# invert.net
KiCad netlist of a schematic drawn in Altium Designer
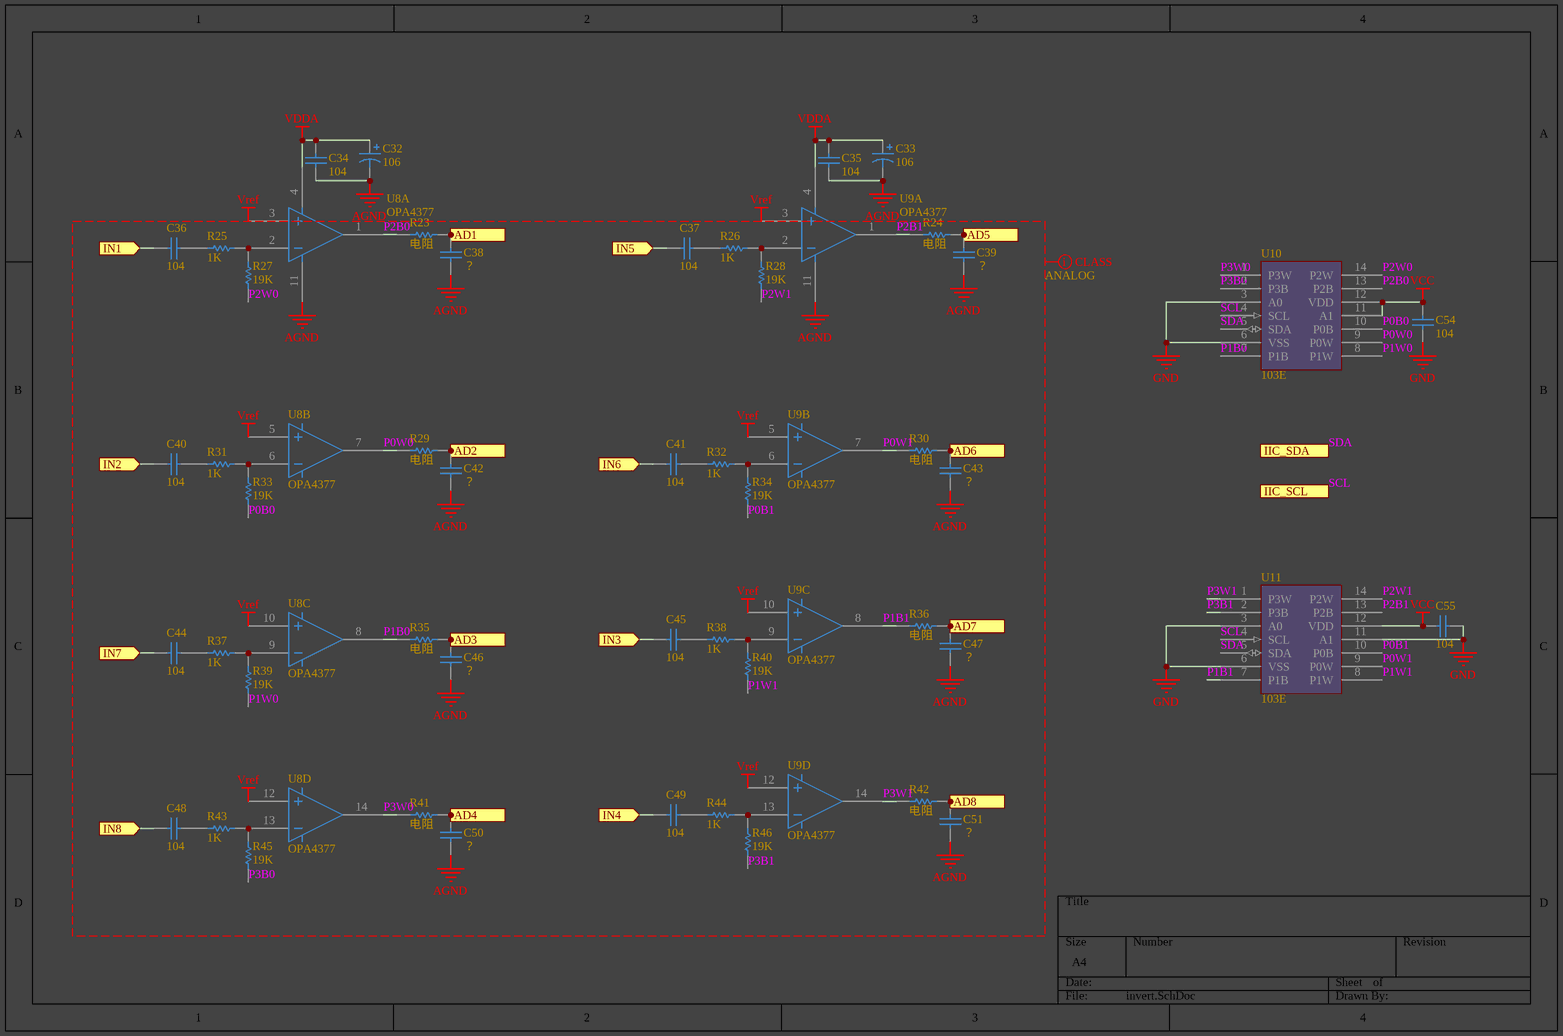
[diagram p0: invert.SchDoc]

(export (version "E")
  (design (tool "Eeschema 10.0.6"))
  (components
    (comp (ref "C32")
      (value "106")
      (footprint "3216-ce")
      (description "Polarized Capacitor (Axial)")
      (fields (field (name "PUBLISHER") "Altium Limited"))
      (libsource (lib "iMag") (part "电解电容"))
    )
    (comp (ref "C33")
      (value "106")
      (footprint "3216-ce")
      (description "Polarized Capacitor (Axial)")
      (fields (field (name "PUBLISHER") "Altium Limited"))
      (libsource (lib "iMag") (part "电解电容"))
    )
    (comp (ref "C34")
      (value "104")
      (footprint "C0402")
      (description "Capacitor")
      (fields (field (name "PUBLISHER") "Altium Limited"))
      (libsource (lib "iMag") (part "电容"))
    )
    (comp (ref "C35")
      (value "104")
      (footprint "C0402")
      (description "Capacitor")
      (fields (field (name "PUBLISHER") "Altium Limited"))
      (libsource (lib "iMag") (part "电容"))
    )
    (comp (ref "C36")
      (value "104")
      (footprint "C0402")
      (description "Capacitor")
      (fields (field (name "PUBLISHER") "Altium Limited"))
      (libsource (lib "iMag") (part "电容"))
    )
    (comp (ref "C37")
      (value "104")
      (footprint "C0402")
      (description "Capacitor")
      (fields (field (name "PUBLISHER") "Altium Limited"))
      (libsource (lib "iMag") (part "电容"))
    )
    (comp (ref "C38")
      (value "？")
      (footprint "C0402")
      (description "Capacitor")
      (fields (field (name "PUBLISHER") "Altium Limited"))
      (libsource (lib "iMag") (part "电容"))
    )
    (comp (ref "C39")
      (value "？")
      (footprint "C0402")
      (description "Capacitor")
      (fields (field (name "PUBLISHER") "Altium Limited"))
      (libsource (lib "iMag") (part "电容"))
    )
    (comp (ref "C40")
      (value "104")
      (footprint "C0402")
      (description "Capacitor")
      (fields (field (name "PUBLISHER") "Altium Limited"))
      (libsource (lib "iMag") (part "电容"))
    )
    (comp (ref "C41")
      (value "104")
      (footprint "C0402")
      (description "Capacitor")
      (fields (field (name "PUBLISHER") "Altium Limited"))
      (libsource (lib "iMag") (part "电容"))
    )
    (comp (ref "C42")
      (value "？")
      (footprint "C0402")
      (description "Capacitor")
      (fields (field (name "PUBLISHER") "Altium Limited"))
      (libsource (lib "iMag") (part "电容"))
    )
    (comp (ref "C43")
      (value "？")
      (footprint "C0402")
      (description "Capacitor")
      (fields (field (name "PUBLISHER") "Altium Limited"))
      (libsource (lib "iMag") (part "电容"))
    )
    (comp (ref "C44")
      (value "104")
      (footprint "C0402")
      (description "Capacitor")
      (fields (field (name "PUBLISHER") "Altium Limited"))
      (libsource (lib "iMag") (part "电容"))
    )
    (comp (ref "C45")
      (value "104")
      (footprint "C0402")
      (description "Capacitor")
      (fields (field (name "PUBLISHER") "Altium Limited"))
      (libsource (lib "iMag") (part "电容"))
    )
    (comp (ref "C46")
      (value "？")
      (footprint "C0402")
      (description "Capacitor")
      (fields (field (name "PUBLISHER") "Altium Limited"))
      (libsource (lib "iMag") (part "电容"))
    )
    (comp (ref "C47")
      (value "？")
      (footprint "C0402")
      (description "Capacitor")
      (fields (field (name "PUBLISHER") "Altium Limited"))
      (libsource (lib "iMag") (part "电容"))
    )
    (comp (ref "C48")
      (value "104")
      (footprint "C0402")
      (description "Capacitor")
      (fields (field (name "PUBLISHER") "Altium Limited"))
      (libsource (lib "iMag") (part "电容"))
    )
    (comp (ref "C49")
      (value "104")
      (footprint "C0402")
      (description "Capacitor")
      (fields (field (name "PUBLISHER") "Altium Limited"))
      (libsource (lib "iMag") (part "电容"))
    )
    (comp (ref "C50")
      (value "？")
      (footprint "C0402")
      (description "Capacitor")
      (fields (field (name "PUBLISHER") "Altium Limited"))
      (libsource (lib "iMag") (part "电容"))
    )
    (comp (ref "C51")
      (value "？")
      (footprint "C0402")
      (description "Capacitor")
      (fields (field (name "PUBLISHER") "Altium Limited"))
      (libsource (lib "iMag") (part "电容"))
    )
    (comp (ref "C54")
      (value "104")
      (footprint "C0603")
      (description "Capacitor")
      (fields (field (name "PUBLISHER") "Altium Limited"))
      (libsource (lib "iMag") (part "电容"))
    )
    (comp (ref "C55")
      (value "104")
      (footprint "C0603")
      (description "Capacitor")
      (fields (field (name "PUBLISHER") "Altium Limited"))
      (libsource (lib "iMag") (part "电容"))
    )
    (comp (ref "R23")
      (value "电阻")
      (footprint "R0402")
      (description "Resistor")
      (fields (field (name "PUBLISHER") "Altium Limited"))
      (libsource (lib "iMag") (part "电阻"))
    )
    (comp (ref "R24")
      (value "电阻")
      (footprint "R0402")
      (description "Resistor")
      (fields (field (name "PUBLISHER") "Altium Limited"))
      (libsource (lib "iMag") (part "电阻"))
    )
    (comp (ref "R25")
      (value "1K")
      (footprint "R0402")
      (description "Resistor")
      (fields (field (name "PUBLISHER") "Altium Limited"))
      (libsource (lib "iMag") (part "电阻"))
    )
    (comp (ref "R26")
      (value "1K")
      (footprint "R0402")
      (description "Resistor")
      (fields (field (name "PUBLISHER") "Altium Limited"))
      (libsource (lib "iMag") (part "电阻"))
    )
    (comp (ref "R27")
      (value "19K")
      (footprint "R0402")
      (description "Resistor")
      (fields (field (name "PUBLISHER") "Altium Limited"))
      (libsource (lib "iMag") (part "电阻"))
    )
    (comp (ref "R28")
      (value "19K")
      (footprint "R0402")
      (description "Resistor")
      (fields (field (name "PUBLISHER") "Altium Limited"))
      (libsource (lib "iMag") (part "电阻"))
    )
    (comp (ref "R29")
      (value "电阻")
      (footprint "R0402")
      (description "Resistor")
      (fields (field (name "PUBLISHER") "Altium Limited"))
      (libsource (lib "iMag") (part "电阻"))
    )
    (comp (ref "R30")
      (value "电阻")
      (footprint "R0402")
      (description "Resistor")
      (fields (field (name "PUBLISHER") "Altium Limited"))
      (libsource (lib "iMag") (part "电阻"))
    )
    (comp (ref "R31")
      (value "1K")
      (footprint "R0402")
      (description "Resistor")
      (fields (field (name "PUBLISHER") "Altium Limited"))
      (libsource (lib "iMag") (part "电阻"))
    )
    (comp (ref "R32")
      (value "1K")
      (footprint "R0402")
      (description "Resistor")
      (fields (field (name "PUBLISHER") "Altium Limited"))
      (libsource (lib "iMag") (part "电阻"))
    )
    (comp (ref "R33")
      (value "19K")
      (footprint "R0402")
      (description "Resistor")
      (fields (field (name "PUBLISHER") "Altium Limited"))
      (libsource (lib "iMag") (part "电阻"))
    )
    (comp (ref "R34")
      (value "19K")
      (footprint "R0402")
      (description "Resistor")
      (fields (field (name "PUBLISHER") "Altium Limited"))
      (libsource (lib "iMag") (part "电阻"))
    )
    (comp (ref "R35")
      (value "电阻")
      (footprint "R0402")
      (description "Resistor")
      (fields (field (name "PUBLISHER") "Altium Limited"))
      (libsource (lib "iMag") (part "电阻"))
    )
    (comp (ref "R36")
      (value "电阻")
      (footprint "R0402")
      (description "Resistor")
      (fields (field (name "PUBLISHER") "Altium Limited"))
      (libsource (lib "iMag") (part "电阻"))
    )
    (comp (ref "R37")
      (value "1K")
      (footprint "R0402")
      (description "Resistor")
      (fields (field (name "PUBLISHER") "Altium Limited"))
      (libsource (lib "iMag") (part "电阻"))
    )
    (comp (ref "R38")
      (value "1K")
      (footprint "R0402")
      (description "Resistor")
      (fields (field (name "PUBLISHER") "Altium Limited"))
      (libsource (lib "iMag") (part "电阻"))
    )
    (comp (ref "R39")
      (value "19K")
      (footprint "R0402")
      (description "Resistor")
      (fields (field (name "PUBLISHER") "Altium Limited"))
      (libsource (lib "iMag") (part "电阻"))
    )
    (comp (ref "R40")
      (value "19K")
      (footprint "R0402")
      (description "Resistor")
      (fields (field (name "PUBLISHER") "Altium Limited"))
      (libsource (lib "iMag") (part "电阻"))
    )
    (comp (ref "R41")
      (value "电阻")
      (footprint "R0402")
      (description "Resistor")
      (fields (field (name "PUBLISHER") "Altium Limited"))
      (libsource (lib "iMag") (part "电阻"))
    )
    (comp (ref "R42")
      (value "电阻")
      (footprint "R0402")
      (description "Resistor")
      (fields (field (name "PUBLISHER") "Altium Limited"))
      (libsource (lib "iMag") (part "电阻"))
    )
    (comp (ref "R43")
      (value "1K")
      (footprint "R0402")
      (description "Resistor")
      (fields (field (name "PUBLISHER") "Altium Limited"))
      (libsource (lib "iMag") (part "电阻"))
    )
    (comp (ref "R44")
      (value "1K")
      (footprint "R0402")
      (description "Resistor")
      (fields (field (name "PUBLISHER") "Altium Limited"))
      (libsource (lib "iMag") (part "电阻"))
    )
    (comp (ref "R45")
      (value "19K")
      (footprint "R0402")
      (description "Resistor")
      (fields (field (name "PUBLISHER") "Altium Limited"))
      (libsource (lib "iMag") (part "电阻"))
    )
    (comp (ref "R46")
      (value "19K")
      (footprint "R0402")
      (description "Resistor")
      (fields (field (name "PUBLISHER") "Altium Limited"))
      (libsource (lib "iMag") (part "电阻"))
    )
    (comp (ref "U8") (value "OPA4377") (footprint "TSSOP-14") (libsource (lib "iMag") (part "4运放")))
    (comp (ref "U9") (value "OPA4377") (footprint "TSSOP-14") (libsource (lib "iMag") (part "4运放")))
    (comp (ref "U10") (value "103E") (footprint "TSSOP-14") (libsource (lib "iMag") (part "MCP4452")))
    (comp (ref "U11") (value "103E") (footprint "TSSOP-14") (libsource (lib "iMag") (part "MCP4452")))
  )
  (nets
    (net (code "1") (name "/AD1") (class "Default")
      (node (ref "C38") (pin "2") (pinfunction "2_2") (pintype "passive"))
      (node (ref "R23") (pin "1") (pinfunction "1_1") (pintype "passive"))
    )
    (net (code "2") (name "/AD2") (class "Default")
      (node (ref "C42") (pin "2") (pinfunction "2_2") (pintype "passive"))
      (node (ref "R29") (pin "1") (pinfunction "1_1") (pintype "passive"))
    )
    (net (code "3") (name "/AD3") (class "Default")
      (node (ref "C46") (pin "2") (pinfunction "2_2") (pintype "passive"))
      (node (ref "R35") (pin "1") (pinfunction "1_1") (pintype "passive"))
    )
    (net (code "4") (name "/AD4") (class "Default")
      (node (ref "C50") (pin "2") (pinfunction "2_2") (pintype "passive"))
      (node (ref "R41") (pin "1") (pinfunction "1_1") (pintype "passive"))
    )
    (net (code "5") (name "/AD5") (class "Default")
      (node (ref "C39") (pin "2") (pinfunction "2_2") (pintype "passive"))
      (node (ref "R24") (pin "1") (pinfunction "1_1") (pintype "passive"))
    )
    (net (code "6") (name "/AD6") (class "Default")
      (node (ref "C43") (pin "2") (pinfunction "2_2") (pintype "passive"))
      (node (ref "R30") (pin "1") (pinfunction "1_1") (pintype "passive"))
    )
    (net (code "7") (name "/AD7") (class "Default")
      (node (ref "C47") (pin "2") (pinfunction "2_2") (pintype "passive"))
      (node (ref "R36") (pin "1") (pinfunction "1_1") (pintype "passive"))
    )
    (net (code "8") (name "/AD8") (class "Default")
      (node (ref "C51") (pin "2") (pinfunction "2_2") (pintype "passive"))
      (node (ref "R42") (pin "1") (pinfunction "1_1") (pintype "passive"))
    )
    (net (code "9") (name "/IN1") (class "Default")
      (node (ref "C36") (pin "1") (pinfunction "1_1") (pintype "passive"))
    )
    (net (code "10") (name "/IN2") (class "Default")
      (node (ref "C40") (pin "1") (pinfunction "1_1") (pintype "passive"))
    )
    (net (code "11") (name "/IN3") (class "Default")
      (node (ref "C45") (pin "1") (pinfunction "1_1") (pintype "passive"))
    )
    (net (code "12") (name "/IN4") (class "Default")
      (node (ref "C49") (pin "1") (pinfunction "1_1") (pintype "passive"))
    )
    (net (code "13") (name "/IN5") (class "Default")
      (node (ref "C37") (pin "1") (pinfunction "1_1") (pintype "passive"))
    )
    (net (code "14") (name "/IN6") (class "Default")
      (node (ref "C41") (pin "1") (pinfunction "1_1") (pintype "passive"))
    )
    (net (code "15") (name "/IN7") (class "Default")
      (node (ref "C44") (pin "1") (pinfunction "1_1") (pintype "passive"))
    )
    (net (code "16") (name "/IN8") (class "Default")
      (node (ref "C48") (pin "1") (pinfunction "1_1") (pintype "passive"))
    )
    (net (code "17") (name "/P0B0") (class "Default")
      (node (ref "R33") (pin "2") (pinfunction "2_2") (pintype "passive"))
      (node (ref "U10") (pin "10") (pinfunction "P0B_10") (pintype "passive"))
    )
    (net (code "18") (name "/P0B1") (class "Default")
      (node (ref "R34") (pin "2") (pinfunction "2_2") (pintype "passive"))
      (node (ref "U11") (pin "10") (pinfunction "P0B_10") (pintype "passive"))
    )
    (net (code "19") (name "/P0W0") (class "Default")
      (node (ref "R29") (pin "2") (pinfunction "2_2") (pintype "passive"))
      (node (ref "U10") (pin "9") (pinfunction "P0W_9") (pintype "passive"))
      (node (ref "U8") (pin "7") (pintype "passive"))
    )
    (net (code "20") (name "/P0W1") (class "Default")
      (node (ref "R30") (pin "2") (pinfunction "2_2") (pintype "passive"))
      (node (ref "U11") (pin "9") (pinfunction "P0W_9") (pintype "passive"))
      (node (ref "U9") (pin "7") (pintype "passive"))
    )
    (net (code "21") (name "/P1B0") (class "Default")
      (node (ref "R35") (pin "2") (pinfunction "2_2") (pintype "passive"))
      (node (ref "U10") (pin "7") (pinfunction "P1B_7") (pintype "passive"))
      (node (ref "U8") (pin "8") (pintype "passive"))
    )
    (net (code "22") (name "/P1B1") (class "Default")
      (node (ref "R36") (pin "2") (pinfunction "2_2") (pintype "passive"))
      (node (ref "U11") (pin "7") (pinfunction "P1B_7") (pintype "passive"))
      (node (ref "U9") (pin "8") (pintype "passive"))
    )
    (net (code "23") (name "/P1W0") (class "Default")
      (node (ref "R39") (pin "2") (pinfunction "2_2") (pintype "passive"))
      (node (ref "U10") (pin "8") (pinfunction "P1W_8") (pintype "passive"))
    )
    (net (code "24") (name "/P1W1") (class "Default")
      (node (ref "R40") (pin "2") (pinfunction "2_2") (pintype "passive"))
      (node (ref "U11") (pin "8") (pinfunction "P1W_8") (pintype "passive"))
    )
    (net (code "25") (name "/P2B0") (class "Default")
      (node (ref "R23") (pin "2") (pinfunction "2_2") (pintype "passive"))
      (node (ref "U10") (pin "13") (pinfunction "P2B_13") (pintype "passive"))
      (node (ref "U8") (pin "1") (pintype "passive"))
    )
    (net (code "26") (name "/P2B1") (class "Default")
      (node (ref "R24") (pin "2") (pinfunction "2_2") (pintype "passive"))
      (node (ref "U11") (pin "13") (pinfunction "P2B_13") (pintype "passive"))
      (node (ref "U9") (pin "1") (pintype "passive"))
    )
    (net (code "27") (name "/P2W0") (class "Default")
      (node (ref "R27") (pin "2") (pinfunction "2_2") (pintype "passive"))
      (node (ref "U10") (pin "14") (pinfunction "P2W_14") (pintype "passive"))
    )
    (net (code "28") (name "/P2W1") (class "Default")
      (node (ref "R28") (pin "2") (pinfunction "2_2") (pintype "passive"))
      (node (ref "U11") (pin "14") (pinfunction "P2W_14") (pintype "passive"))
    )
    (net (code "29") (name "/P3B0") (class "Default")
      (node (ref "R45") (pin "2") (pinfunction "2_2") (pintype "passive"))
      (node (ref "U10") (pin "2") (pinfunction "P3B_2") (pintype "passive"))
    )
    (net (code "30") (name "/P3B1") (class "Default")
      (node (ref "R46") (pin "2") (pinfunction "2_2") (pintype "passive"))
      (node (ref "U11") (pin "2") (pinfunction "P3B_2") (pintype "passive"))
    )
    (net (code "31") (name "/P3W0") (class "Default")
      (node (ref "R41") (pin "2") (pinfunction "2_2") (pintype "passive"))
      (node (ref "U10") (pin "1") (pinfunction "P3W_1") (pintype "passive"))
      (node (ref "U8") (pin "14") (pintype "passive"))
    )
    (net (code "32") (name "/P3W1") (class "Default")
      (node (ref "R42") (pin "2") (pinfunction "2_2") (pintype "passive"))
      (node (ref "U11") (pin "1") (pinfunction "P3W_1") (pintype "passive"))
      (node (ref "U9") (pin "14") (pintype "passive"))
    )
    (net (code "33") (name "/SCL") (class "Default")
      (node (ref "U10") (pin "4") (pinfunction "SCL_4") (pintype "input"))
      (node (ref "U11") (pin "4") (pinfunction "SCL_4") (pintype "input"))
    )
    (net (code "34") (name "/SDA") (class "Default")
      (node (ref "U10") (pin "5") (pinfunction "SDA_5") (pintype "bidirectional"))
      (node (ref "U11") (pin "5") (pinfunction "SDA_5") (pintype "bidirectional"))
    )
    (net (code "35") (name "AGND") (class "Default")
      (node (ref "C32") (pin "2") (pinfunction "2_2") (pintype "passive"))
      (node (ref "C33") (pin "2") (pinfunction "2_2") (pintype "passive"))
      (node (ref "C34") (pin "1") (pinfunction "1_1") (pintype "passive"))
      (node (ref "C35") (pin "1") (pinfunction "1_1") (pintype "passive"))
      (node (ref "C38") (pin "1") (pinfunction "1_1") (pintype "passive"))
      (node (ref "C39") (pin "1") (pinfunction "1_1") (pintype "passive"))
      (node (ref "C42") (pin "1") (pinfunction "1_1") (pintype "passive"))
      (node (ref "C43") (pin "1") (pinfunction "1_1") (pintype "passive"))
      (node (ref "C46") (pin "1") (pinfunction "1_1") (pintype "passive"))
      (node (ref "C47") (pin "1") (pinfunction "1_1") (pintype "passive"))
      (node (ref "C50") (pin "1") (pinfunction "1_1") (pintype "passive"))
      (node (ref "C51") (pin "1") (pinfunction "1_1") (pintype "passive"))
      (node (ref "U8") (pin "11") (pintype "passive"))
      (node (ref "U9") (pin "11") (pintype "passive"))
    )
    (net (code "36") (name "GND") (class "Default")
      (node (ref "C54") (pin "1") (pinfunction "1_1") (pintype "passive"))
      (node (ref "C55") (pin "2") (pinfunction "2_2") (pintype "passive"))
      (node (ref "U10") (pin "3") (pinfunction "A0_3") (pintype "passive"))
      (node (ref "U10") (pin "6") (pinfunction "VSS_6") (pintype "passive"))
      (node (ref "U11") (pin "11") (pinfunction "A1_11") (pintype "passive"))
      (node (ref "U11") (pin "3") (pinfunction "A0_3") (pintype "passive"))
      (node (ref "U11") (pin "6") (pinfunction "VSS_6") (pintype "passive"))
    )
    (net (code "37") (name "Net-(C36-Pad2)") (class "Default")
      (node (ref "C36") (pin "2") (pinfunction "2_2") (pintype "passive"))
      (node (ref "R25") (pin "2") (pinfunction "2_2") (pintype "passive"))
    )
    (net (code "38") (name "Net-(C37-Pad2)") (class "Default")
      (node (ref "C37") (pin "2") (pinfunction "2_2") (pintype "passive"))
      (node (ref "R26") (pin "2") (pinfunction "2_2") (pintype "passive"))
    )
    (net (code "39") (name "Net-(C40-Pad2)") (class "Default")
      (node (ref "C40") (pin "2") (pinfunction "2_2") (pintype "passive"))
      (node (ref "R31") (pin "2") (pinfunction "2_2") (pintype "passive"))
    )
    (net (code "40") (name "Net-(C41-Pad2)") (class "Default")
      (node (ref "C41") (pin "2") (pinfunction "2_2") (pintype "passive"))
      (node (ref "R32") (pin "2") (pinfunction "2_2") (pintype "passive"))
    )
    (net (code "41") (name "Net-(C44-Pad2)") (class "Default")
      (node (ref "C44") (pin "2") (pinfunction "2_2") (pintype "passive"))
      (node (ref "R37") (pin "2") (pinfunction "2_2") (pintype "passive"))
    )
    (net (code "42") (name "Net-(C45-Pad2)") (class "Default")
      (node (ref "C45") (pin "2") (pinfunction "2_2") (pintype "passive"))
      (node (ref "R38") (pin "2") (pinfunction "2_2") (pintype "passive"))
    )
    (net (code "43") (name "Net-(C48-Pad2)") (class "Default")
      (node (ref "C48") (pin "2") (pinfunction "2_2") (pintype "passive"))
      (node (ref "R43") (pin "2") (pinfunction "2_2") (pintype "passive"))
    )
    (net (code "44") (name "Net-(C49-Pad2)") (class "Default")
      (node (ref "C49") (pin "2") (pinfunction "2_2") (pintype "passive"))
      (node (ref "R44") (pin "2") (pinfunction "2_2") (pintype "passive"))
    )
    (net (code "45") (name "Net-(R25-Pad1)") (class "Default")
      (node (ref "R25") (pin "1") (pinfunction "1_1") (pintype "passive"))
      (node (ref "R27") (pin "1") (pinfunction "1_1") (pintype "passive"))
      (node (ref "U8") (pin "2") (pintype "passive"))
    )
    (net (code "46") (name "Net-(R26-Pad1)") (class "Default")
      (node (ref "R26") (pin "1") (pinfunction "1_1") (pintype "passive"))
      (node (ref "R28") (pin "1") (pinfunction "1_1") (pintype "passive"))
      (node (ref "U9") (pin "2") (pintype "passive"))
    )
    (net (code "47") (name "Net-(R31-Pad1)") (class "Default")
      (node (ref "R31") (pin "1") (pinfunction "1_1") (pintype "passive"))
      (node (ref "R33") (pin "1") (pinfunction "1_1") (pintype "passive"))
      (node (ref "U8") (pin "6") (pintype "passive"))
    )
    (net (code "48") (name "Net-(R32-Pad1)") (class "Default")
      (node (ref "R32") (pin "1") (pinfunction "1_1") (pintype "passive"))
      (node (ref "R34") (pin "1") (pinfunction "1_1") (pintype "passive"))
      (node (ref "U9") (pin "6") (pintype "passive"))
    )
    (net (code "49") (name "Net-(R37-Pad1)") (class "Default")
      (node (ref "R37") (pin "1") (pinfunction "1_1") (pintype "passive"))
      (node (ref "R39") (pin "1") (pinfunction "1_1") (pintype "passive"))
      (node (ref "U8") (pin "9") (pintype "passive"))
    )
    (net (code "50") (name "Net-(R38-Pad1)") (class "Default")
      (node (ref "R38") (pin "1") (pinfunction "1_1") (pintype "passive"))
      (node (ref "R40") (pin "1") (pinfunction "1_1") (pintype "passive"))
      (node (ref "U9") (pin "9") (pintype "passive"))
    )
    (net (code "51") (name "Net-(R43-Pad1)") (class "Default")
      (node (ref "R43") (pin "1") (pinfunction "1_1") (pintype "passive"))
      (node (ref "R45") (pin "1") (pinfunction "1_1") (pintype "passive"))
      (node (ref "U8") (pin "13") (pintype "passive"))
    )
    (net (code "52") (name "Net-(R44-Pad1)") (class "Default")
      (node (ref "R44") (pin "1") (pinfunction "1_1") (pintype "passive"))
      (node (ref "R46") (pin "1") (pinfunction "1_1") (pintype "passive"))
      (node (ref "U9") (pin "13") (pintype "passive"))
    )
    (net (code "53") (name "VCC") (class "Default")
      (node (ref "C54") (pin "2") (pinfunction "2_2") (pintype "passive"))
      (node (ref "C55") (pin "1") (pinfunction "1_1") (pintype "passive"))
      (node (ref "U10") (pin "11") (pinfunction "A1_11") (pintype "passive"))
      (node (ref "U10") (pin "12") (pinfunction "VDD_12") (pintype "passive"))
      (node (ref "U11") (pin "12") (pinfunction "VDD_12") (pintype "passive"))
    )
    (net (code "54") (name "VDDA") (class "Default")
      (node (ref "C32") (pin "1") (pinfunction "1_1") (pintype "passive"))
      (node (ref "C33") (pin "1") (pinfunction "1_1") (pintype "passive"))
      (node (ref "C34") (pin "2") (pinfunction "2_2") (pintype "passive"))
      (node (ref "C35") (pin "2") (pinfunction "2_2") (pintype "passive"))
      (node (ref "U8") (pin "4") (pintype "passive"))
      (node (ref "U9") (pin "4") (pintype "passive"))
    )
    (net (code "55") (name "Vref") (class "Default")
      (node (ref "U8") (pin "10") (pintype "passive"))
      (node (ref "U8") (pin "12") (pintype "passive"))
      (node (ref "U8") (pin "3") (pintype "passive"))
      (node (ref "U8") (pin "5") (pintype "passive"))
      (node (ref "U9") (pin "10") (pintype "passive"))
      (node (ref "U9") (pin "12") (pintype "passive"))
      (node (ref "U9") (pin "3") (pintype "passive"))
      (node (ref "U9") (pin "5") (pintype "passive"))
    )
  )
)
